# sam4_iot.net
KiCad netlist of a schematic drawn in EAGLE
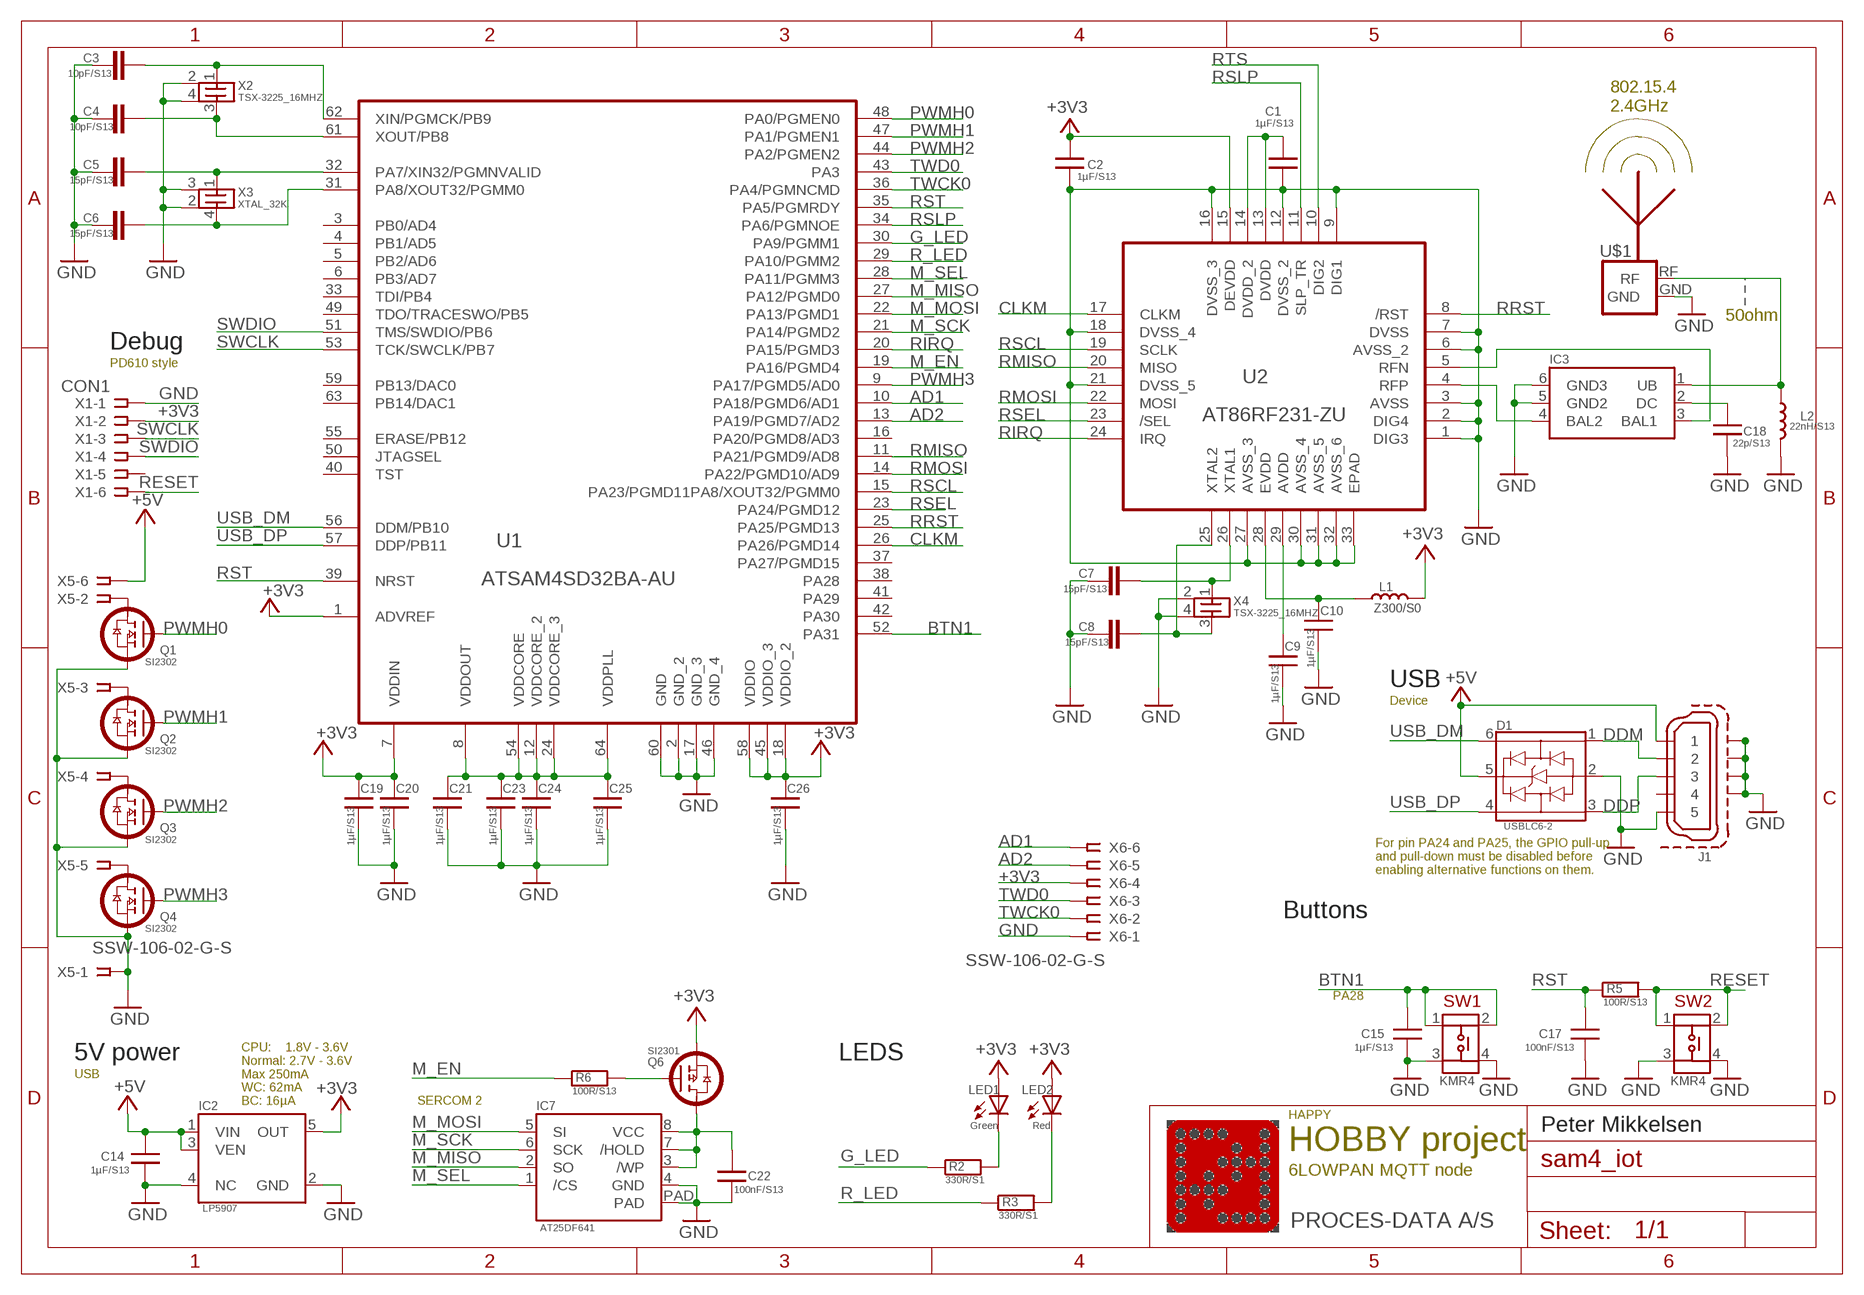
[diagram p0: schematic, sheet 1]

(export (version "E")
  (design (tool "Eeschema 10.0.6"))
  (components
    (comp (ref "C1")
      (value "1µF/S13")
      (footprint "eagle-import:C0603")
      (libsource (lib "eagle-import") (part "C-EUC0603"))
    )
    (comp (ref "C2")
      (value "1µF/S13")
      (footprint "eagle-import:C0603")
      (libsource (lib "eagle-import") (part "C-EUC0603"))
    )
    (comp (ref "C3")
      (value "10pF/S13")
      (footprint "eagle-import:C0603")
      (libsource (lib "eagle-import") (part "rcl_334_C-EUC0603"))
    )
    (comp (ref "C4")
      (value "10pF/S13")
      (footprint "eagle-import:C0603")
      (libsource (lib "eagle-import") (part "rcl_334_C-EUC0603"))
    )
    (comp (ref "C5")
      (value "15pF/S13")
      (footprint "eagle-import:C0603")
      (libsource (lib "eagle-import") (part "rcl_334_C-EUC0603"))
    )
    (comp (ref "C6")
      (value "15pF/S13")
      (footprint "eagle-import:C0603")
      (libsource (lib "eagle-import") (part "rcl_334_C-EUC0603"))
    )
    (comp (ref "C7")
      (value "15pF/S13")
      (footprint "eagle-import:C0603")
      (libsource (lib "eagle-import") (part "rcl_334_C-EUC0603"))
    )
    (comp (ref "C8")
      (value "15pF/S13")
      (footprint "eagle-import:C0603")
      (libsource (lib "eagle-import") (part "rcl_334_C-EUC0603"))
    )
    (comp (ref "C9")
      (value "1µF/S13")
      (footprint "eagle-import:C0603")
      (libsource (lib "eagle-import") (part "C-EUC0603"))
    )
    (comp (ref "C10")
      (value "1µF/S13")
      (footprint "eagle-import:C0603")
      (libsource (lib "eagle-import") (part "C-EUC0603"))
    )
    (comp (ref "C14")
      (value "1µF/S13")
      (footprint "eagle-import:C0603")
      (libsource (lib "eagle-import") (part "C-EUC0603"))
    )
    (comp (ref "C15")
      (value "1µF/S13")
      (footprint "eagle-import:C0603")
      (libsource (lib "eagle-import") (part "C-EUC0603"))
    )
    (comp (ref "C17")
      (value "100nF/S13")
      (footprint "eagle-import:C0603")
      (libsource (lib "eagle-import") (part "C-EUC0603"))
    )
    (comp (ref "C18")
      (value "22p/S13")
      (footprint "eagle-import:C0603")
      (libsource (lib "eagle-import") (part "C-EUC0603"))
    )
    (comp (ref "C19")
      (value "1µF/S13")
      (footprint "eagle-import:C0603")
      (libsource (lib "eagle-import") (part "C-EUC0603"))
    )
    (comp (ref "C20")
      (value "1µF/S13")
      (footprint "eagle-import:C0603")
      (libsource (lib "eagle-import") (part "C-EUC0603"))
    )
    (comp (ref "C21")
      (value "1µF/S13")
      (footprint "eagle-import:C0603")
      (libsource (lib "eagle-import") (part "C-EUC0603"))
    )
    (comp (ref "C22")
      (value "100nF/S13")
      (footprint "eagle-import:C0603")
      (libsource (lib "eagle-import") (part "C-EUC0603"))
    )
    (comp (ref "C23")
      (value "1µF/S13")
      (footprint "eagle-import:C0603")
      (libsource (lib "eagle-import") (part "C-EUC0603"))
    )
    (comp (ref "C24")
      (value "1µF/S13")
      (footprint "eagle-import:C0603")
      (libsource (lib "eagle-import") (part "C-EUC0603"))
    )
    (comp (ref "C25")
      (value "1µF/S13")
      (footprint "eagle-import:C0603")
      (libsource (lib "eagle-import") (part "C-EUC0603"))
    )
    (comp (ref "C26")
      (value "1µF/S13")
      (footprint "eagle-import:C0603")
      (libsource (lib "eagle-import") (part "C-EUC0603"))
    )
    (comp (ref "D1")
      (value "USBLC6-2")
      (footprint "eagle-import:SOT_6")
      (libsource (lib "eagle-import") (part "USBLC6-2"))
    )
    (comp (ref "IC2")
      (value "LP5907")
      (footprint "eagle-import:SOT23-5")
      (libsource (lib "eagle-import") (part "LP5907"))
    )
    (comp (ref "IC3")
      (value "BALUN")
      (footprint "eagle-import:2450BM15A0002")
      (libsource (lib "eagle-import") (part "BALUN"))
    )
    (comp (ref "IC7")
      (value "AT25DF641")
      (footprint "eagle-import:VDFN_8MW1")
      (libsource (lib "eagle-import") (part "AT25DF641"))
    )
    (comp (ref "J1")
      (value "MICROUSB")
      (footprint "eagle-import:MICROUSB")
      (libsource (lib "eagle-import") (part "MICROUSB"))
    )
    (comp (ref "L1")
      (value "Z300/S0")
      (footprint "eagle-import:L0603")
      (libsource (lib "eagle-import") (part "L0603"))
    )
    (comp (ref "L2")
      (value "22nH/S13")
      (footprint "eagle-import:L0603")
      (libsource (lib "eagle-import") (part "L0603"))
    )
    (comp (ref "LED1")
      (value "Green")
      (footprint "eagle-import:OSRAM-MINI-TOP-LED")
      (libsource (lib "eagle-import") (part "LEDMINI-TOP"))
    )
    (comp (ref "LED2")
      (value "Red")
      (footprint "eagle-import:OSRAM-MINI-TOP-LED")
      (libsource (lib "eagle-import") (part "LEDMINI-TOP"))
    )
    (comp (ref "Q1")
      (value "SI2302")
      (footprint "eagle-import:TO-236(SOT23)")
      (libsource (lib "eagle-import") (part "SI2302"))
    )
    (comp (ref "Q2")
      (value "SI2302")
      (footprint "eagle-import:TO-236(SOT23)")
      (libsource (lib "eagle-import") (part "SI2302"))
    )
    (comp (ref "Q3")
      (value "SI2302")
      (footprint "eagle-import:TO-236(SOT23)")
      (libsource (lib "eagle-import") (part "SI2302"))
    )
    (comp (ref "Q4")
      (value "SI2302")
      (footprint "eagle-import:TO-236(SOT23)")
      (libsource (lib "eagle-import") (part "SI2302"))
    )
    (comp (ref "Q6")
      (value "SI2301")
      (footprint "eagle-import:TO-236(SOT23)")
      (libsource (lib "eagle-import") (part "SI2301"))
    )
    (comp (ref "R2")
      (value "330R/S1")
      (footprint "eagle-import:R1206")
      (libsource (lib "eagle-import") (part "R-EU_R1206"))
    )
    (comp (ref "R3")
      (value "330R/S1")
      (footprint "eagle-import:R1206")
      (libsource (lib "eagle-import") (part "R-EU_R1206"))
    )
    (comp (ref "R5")
      (value "100R/S13")
      (footprint "eagle-import:R0603")
      (libsource (lib "eagle-import") (part "R-EU_R0603"))
    )
    (comp (ref "R6")
      (value "100R/S13")
      (footprint "eagle-import:R0603")
      (libsource (lib "eagle-import") (part "R-EU_R0603"))
    )
    (comp (ref "SW1")
      (value "KMR4")
      (footprint "eagle-import:KMR4")
      (libsource (lib "eagle-import") (part "KMR4"))
    )
    (comp (ref "SW2")
      (value "KMR4")
      (footprint "eagle-import:KMR4")
      (libsource (lib "eagle-import") (part "KMR4"))
    )
    (comp (ref "U$1")
      (value "ANTENNA_1RIGHT")
      (footprint "eagle-import:SWRA117D_RIGHT")
      (libsource (lib "eagle-import") (part "ANTENNA_1RIGHT"))
    )
    (comp (ref "U1")
      (value "ATSAM4SD32BA-AU")
      (footprint "eagle-import:QFP50P1200X1200X160-64N")
      (fields (field (name "MPN") "ATSAM3S4BA-AU"))
      (libsource (lib "eagle-import") (part "ATSAM4SD32BA-AU"))
    )
    (comp (ref "U2")
      (value "AT86RF231-ZU")
      (footprint "eagle-import:QFN50P500X500X100-32N")
      (libsource (lib "eagle-import") (part "AT86RF231-ZU"))
    )
    (comp (ref "X1")
      (value "CON1")
      (footprint "eagle-import:SSW-103-02-S-D")
      (fields (field (name "MPN") "SSW-103-02-S-D"))
      (libsource (lib "eagle-import") (part "SSW-103-02-S-D"))
    )
    (comp (ref "X2")
      (value "TSX-3225_16MHZ")
      (footprint "eagle-import:TSX-3225")
      (libsource (lib "eagle-import") (part "TSX-3225_16MHZ"))
    )
    (comp (ref "X3")
      (value "XTAL_32K")
      (footprint "eagle-import:CM200S")
      (libsource (lib "eagle-import") (part "XTAL_32K"))
    )
    (comp (ref "X4")
      (value "TSX-3225_16MHZ")
      (footprint "eagle-import:TSX-3225")
      (libsource (lib "eagle-import") (part "TSX-3225_16MHZ"))
    )
    (comp (ref "X5")
      (value "SSW-106-02-G-S")
      (footprint "eagle-import:SSW-106-02-G-S")
      (fields (field (name "MF") "Samtec Inc."))
      (libsource (lib "eagle-import") (part "SSW-106-02-G-S"))
    )
    (comp (ref "X6")
      (value "SSW-106-02-G-S")
      (footprint "eagle-import:SSW-106-02-G-S")
      (fields (field (name "MF") "Samtec Inc."))
      (libsource (lib "eagle-import") (part "SSW-106-02-G-S"))
    )
  )
  (nets
    (net (code "1") (name "+3V3") (class "Default")
      (node (ref "C19") (pin "1") (pinfunction "1_1") (pintype "passive"))
      (node (ref "C2") (pin "1") (pinfunction "1_1") (pintype "passive"))
      (node (ref "C20") (pin "1") (pinfunction "1_1") (pintype "passive"))
      (node (ref "C26") (pin "1") (pinfunction "1_1") (pintype "passive"))
      (node (ref "IC2") (pin "5") (pinfunction "OUT_5") (pintype "bidirectional"))
      (node (ref "L1") (pin "P$1") (pinfunction "1_P$1") (pintype "bidirectional"))
      (node (ref "LED1") (pin "A") (pinfunction "A_A") (pintype "passive"))
      (node (ref "LED2") (pin "A") (pinfunction "A_A") (pintype "passive"))
      (node (ref "Q6") (pin "3") (pinfunction "S_3") (pintype "bidirectional"))
      (node (ref "U1") (pin "1") (pinfunction "ADVREF_1") (pintype "input"))
      (node (ref "U1") (pin "18") (pinfunction "VDDIO_2_18") (pintype "power_in"))
      (node (ref "U1") (pin "45") (pinfunction "VDDIO_3_45") (pintype "power_in"))
      (node (ref "U1") (pin "58") (pinfunction "VDDIO_58") (pintype "power_in"))
      (node (ref "U1") (pin "7") (pinfunction "VDDIN_7") (pintype "power_in"))
      (node (ref "U2") (pin "15") (pinfunction "DEVDD_15") (pintype "power_in"))
      (node (ref "X1") (pin "2") (pinfunction "1_2") (pintype "passive"))
      (node (ref "X6") (pin "4") (pinfunction "1_4") (pintype "passive"))
    )
    (net (code "2") (name "+5V") (class "Default")
      (node (ref "C14") (pin "1") (pinfunction "1_1") (pintype "passive"))
      (node (ref "D1") (pin "5") (pinfunction "5_5") (pintype "bidirectional"))
      (node (ref "IC2") (pin "1") (pinfunction "VIN_1") (pintype "bidirectional"))
      (node (ref "IC2") (pin "3") (pinfunction "VEN_3") (pintype "bidirectional"))
      (node (ref "J1") (pin "1") (pinfunction "1_1") (pintype "bidirectional"))
      (node (ref "X5") (pin "6") (pinfunction "1_6") (pintype "passive"))
    )
    (net (code "3") (name "/AD1") (class "Default")
      (node (ref "U1") (pin "10") (pinfunction "PA18/PGMD6/AD1_10") (pintype "bidirectional"))
      (node (ref "X6") (pin "6") (pinfunction "1_6") (pintype "passive"))
    )
    (net (code "4") (name "/AD2") (class "Default")
      (node (ref "U1") (pin "13") (pinfunction "PA19/PGMD7/AD2_13") (pintype "bidirectional"))
      (node (ref "X6") (pin "5") (pinfunction "1_5") (pintype "passive"))
    )
    (net (code "5") (name "/BTN1") (class "Default")
      (node (ref "C15") (pin "1") (pinfunction "1_1") (pintype "passive"))
      (node (ref "SW1") (pin "1") (pinfunction "1_1") (pintype "bidirectional"))
      (node (ref "SW1") (pin "2") (pinfunction "3_2") (pintype "bidirectional"))
      (node (ref "U1") (pin "52") (pinfunction "PA31_52") (pintype "bidirectional"))
    )
    (net (code "6") (name "/CLKM") (class "Default")
      (node (ref "U1") (pin "26") (pinfunction "PA26/PGMD14_26") (pintype "bidirectional"))
      (node (ref "U2") (pin "17") (pinfunction "CLKM_17") (pintype "input"))
    )
    (net (code "7") (name "/DDM") (class "Default")
      (node (ref "D1") (pin "1") (pinfunction "1_1") (pintype "bidirectional"))
      (node (ref "J1") (pin "2") (pinfunction "2_2") (pintype "bidirectional"))
    )
    (net (code "8") (name "/DDP") (class "Default")
      (node (ref "D1") (pin "3") (pinfunction "3_3") (pintype "bidirectional"))
      (node (ref "J1") (pin "3") (pinfunction "3_3") (pintype "bidirectional"))
    )
    (net (code "9") (name "/G_LED") (class "Default")
      (node (ref "R2") (pin "1") (pinfunction "1_1") (pintype "passive"))
      (node (ref "U1") (pin "30") (pinfunction "PA9/PGMM1_30") (pintype "bidirectional"))
    )
    (net (code "10") (name "/M_EN") (class "Default")
      (node (ref "R6") (pin "1") (pinfunction "1_1") (pintype "passive"))
      (node (ref "U1") (pin "19") (pinfunction "PA16/PGMD4_19") (pintype "bidirectional"))
    )
    (net (code "11") (name "/M_MISO") (class "Default")
      (node (ref "IC7") (pin "2") (pinfunction "SO_2") (pintype "bidirectional"))
      (node (ref "U1") (pin "27") (pinfunction "PA12/PGMD0_27") (pintype "bidirectional"))
    )
    (net (code "12") (name "/M_MOSI") (class "Default")
      (node (ref "IC7") (pin "5") (pinfunction "SI_5") (pintype "bidirectional"))
      (node (ref "U1") (pin "22") (pinfunction "PA13/PGMD1_22") (pintype "bidirectional"))
    )
    (net (code "13") (name "/M_SCK") (class "Default")
      (node (ref "IC7") (pin "6") (pinfunction "SCK_6") (pintype "bidirectional"))
      (node (ref "U1") (pin "21") (pinfunction "PA14/PGMD2_21") (pintype "bidirectional"))
    )
    (net (code "14") (name "/M_SEL") (class "Default")
      (node (ref "IC7") (pin "1") (pinfunction "/CS_1") (pintype "bidirectional"))
      (node (ref "U1") (pin "28") (pinfunction "PA11/PGMM3_28") (pintype "bidirectional"))
    )
    (net (code "15") (name "/PWMH0") (class "Default")
      (node (ref "Q1") (pin "1") (pinfunction "G_1") (pintype "bidirectional"))
      (node (ref "U1") (pin "48") (pinfunction "PA0/PGMEN0_48") (pintype "bidirectional"))
    )
    (net (code "16") (name "/PWMH1") (class "Default")
      (node (ref "Q2") (pin "1") (pinfunction "G_1") (pintype "bidirectional"))
      (node (ref "U1") (pin "47") (pinfunction "PA1/PGMEN1_47") (pintype "bidirectional"))
    )
    (net (code "17") (name "/PWMH2") (class "Default")
      (node (ref "Q3") (pin "1") (pinfunction "G_1") (pintype "bidirectional"))
      (node (ref "U1") (pin "44") (pinfunction "PA2/PGMEN2_44") (pintype "bidirectional"))
    )
    (net (code "18") (name "/PWMH3") (class "Default")
      (node (ref "Q4") (pin "1") (pinfunction "G_1") (pintype "bidirectional"))
      (node (ref "U1") (pin "9") (pinfunction "PA17/PGMD5/AD0_9") (pintype "bidirectional"))
    )
    (net (code "19") (name "/RESET") (class "Default")
      (node (ref "R5") (pin "2") (pinfunction "2_2") (pintype "passive"))
      (node (ref "SW2") (pin "1") (pinfunction "1_1") (pintype "bidirectional"))
      (node (ref "SW2") (pin "2") (pinfunction "3_2") (pintype "bidirectional"))
      (node (ref "X1") (pin "6") (pinfunction "1_6") (pintype "passive"))
    )
    (net (code "20") (name "/RIRQ") (class "Default")
      (node (ref "U1") (pin "20") (pinfunction "PA15/PGMD3_20") (pintype "bidirectional"))
      (node (ref "U2") (pin "24") (pinfunction "IRQ_24") (pintype "input"))
    )
    (net (code "21") (name "/RMISO") (class "Default")
      (node (ref "U1") (pin "11") (pinfunction "PA21/PGMD9/AD8_11") (pintype "bidirectional"))
      (node (ref "U2") (pin "20") (pinfunction "MISO_20") (pintype "output"))
    )
    (net (code "22") (name "/RMOSI") (class "Default")
      (node (ref "U1") (pin "14") (pinfunction "PA22/PGMD10/AD9_14") (pintype "bidirectional"))
      (node (ref "U2") (pin "22") (pinfunction "MOSI_22") (pintype "input"))
    )
    (net (code "23") (name "/RRST") (class "Default")
      (node (ref "U1") (pin "25") (pinfunction "PA25/PGMD13_25") (pintype "bidirectional"))
      (node (ref "U2") (pin "8") (pinfunction "/RST_8") (pintype "input"))
    )
    (net (code "24") (name "/RSCL") (class "Default")
      (node (ref "U1") (pin "15") (pinfunction "PA23/PGMD11PA8/XOUT32/PGMM0_15") (pintype "bidirectional"))
      (node (ref "U2") (pin "19") (pinfunction "SCLK_19") (pintype "input"))
    )
    (net (code "25") (name "/RSEL") (class "Default")
      (node (ref "U1") (pin "23") (pinfunction "PA24/PGMD12_23") (pintype "bidirectional"))
      (node (ref "U2") (pin "23") (pinfunction "/SEL_23") (pintype "input"))
    )
    (net (code "26") (name "/RSLP") (class "Default")
      (node (ref "U1") (pin "34") (pinfunction "PA6/PGMNOE_34") (pintype "bidirectional"))
      (node (ref "U2") (pin "11") (pinfunction "SLP_TR_11") (pintype "input"))
    )
    (net (code "27") (name "/RST") (class "Default")
      (node (ref "C17") (pin "1") (pinfunction "1_1") (pintype "passive"))
      (node (ref "R5") (pin "1") (pinfunction "1_1") (pintype "passive"))
      (node (ref "U1") (pin "35") (pinfunction "PA5/PGMRDY_35") (pintype "bidirectional"))
      (node (ref "U1") (pin "39") (pinfunction "NRST_39") (pintype "bidirectional"))
    )
    (net (code "28") (name "/RTS") (class "Default")
      (node (ref "U2") (pin "10") (pinfunction "DIG2_10") (pintype "output"))
    )
    (net (code "29") (name "/R_LED") (class "Default")
      (node (ref "R3") (pin "1") (pinfunction "1_1") (pintype "passive"))
      (node (ref "U1") (pin "29") (pinfunction "PA10/PGMM2_29") (pintype "bidirectional"))
    )
    (net (code "30") (name "/SWCLK") (class "Default")
      (node (ref "U1") (pin "53") (pinfunction "TCK/SWCLK/PB7_53") (pintype "bidirectional"))
      (node (ref "X1") (pin "3") (pinfunction "1_3") (pintype "passive"))
    )
    (net (code "31") (name "/SWDIO") (class "Default")
      (node (ref "U1") (pin "51") (pinfunction "TMS/SWDIO/PB6_51") (pintype "bidirectional"))
      (node (ref "X1") (pin "4") (pinfunction "1_4") (pintype "passive"))
    )
    (net (code "32") (name "/TWCK0") (class "Default")
      (node (ref "U1") (pin "36") (pinfunction "PA4/PGMNCMD_36") (pintype "bidirectional"))
      (node (ref "X6") (pin "2") (pinfunction "1_2") (pintype "passive"))
    )
    (net (code "33") (name "/TWD0") (class "Default")
      (node (ref "U1") (pin "43") (pinfunction "PA3_43") (pintype "bidirectional"))
      (node (ref "X6") (pin "3") (pinfunction "1_3") (pintype "passive"))
    )
    (net (code "34") (name "/USB_DM") (class "Default")
      (node (ref "D1") (pin "6") (pinfunction "6_6") (pintype "bidirectional"))
      (node (ref "U1") (pin "56") (pinfunction "DDM/PB10_56") (pintype "bidirectional"))
    )
    (net (code "35") (name "/USB_DP") (class "Default")
      (node (ref "D1") (pin "4") (pinfunction "4_4") (pintype "bidirectional"))
      (node (ref "U1") (pin "57") (pinfunction "DDP/PB11_57") (pintype "bidirectional"))
    )
    (net (code "36") (name "GND") (class "Default")
      (node (ref "C1") (pin "2") (pinfunction "2_2") (pintype "passive"))
      (node (ref "C10") (pin "2") (pinfunction "2_2") (pintype "passive"))
      (node (ref "C14") (pin "2") (pinfunction "2_2") (pintype "passive"))
      (node (ref "C15") (pin "2") (pinfunction "2_2") (pintype "passive"))
      (node (ref "C17") (pin "2") (pinfunction "2_2") (pintype "passive"))
      (node (ref "C18") (pin "2") (pinfunction "2_2") (pintype "passive"))
      (node (ref "C19") (pin "2") (pinfunction "2_2") (pintype "passive"))
      (node (ref "C2") (pin "2") (pinfunction "2_2") (pintype "passive"))
      (node (ref "C20") (pin "2") (pinfunction "2_2") (pintype "passive"))
      (node (ref "C21") (pin "2") (pinfunction "2_2") (pintype "passive"))
      (node (ref "C22") (pin "2") (pinfunction "2_2") (pintype "passive"))
      (node (ref "C23") (pin "2") (pinfunction "2_2") (pintype "passive"))
      (node (ref "C24") (pin "2") (pinfunction "2_2") (pintype "passive"))
      (node (ref "C25") (pin "2") (pinfunction "2_2") (pintype "passive"))
      (node (ref "C26") (pin "2") (pinfunction "2_2") (pintype "passive"))
      (node (ref "C3") (pin "1") (pinfunction "1_1") (pintype "passive"))
      (node (ref "C4") (pin "1") (pinfunction "1_1") (pintype "passive"))
      (node (ref "C5") (pin "1") (pinfunction "1_1") (pintype "passive"))
      (node (ref "C6") (pin "1") (pinfunction "1_1") (pintype "passive"))
      (node (ref "C7") (pin "1") (pinfunction "1_1") (pintype "passive"))
      (node (ref "C8") (pin "1") (pinfunction "1_1") (pintype "passive"))
      (node (ref "C9") (pin "2") (pinfunction "2_2") (pintype "passive"))
      (node (ref "D1") (pin "2") (pinfunction "2_2") (pintype "bidirectional"))
      (node (ref "IC2") (pin "2") (pinfunction "GND_2") (pintype "bidirectional"))
      (node (ref "IC2") (pin "4") (pinfunction "NC_4") (pintype "bidirectional"))
      (node (ref "IC3") (pin "5") (pinfunction "GND2_5") (pintype "bidirectional"))
      (node (ref "IC3") (pin "6") (pinfunction "GND3_6") (pintype "bidirectional"))
      (node (ref "IC7") (pin "4") (pinfunction "GND_4") (pintype "bidirectional"))
      (node (ref "IC7") (pin "PAD") (pinfunction "PAD_PAD") (pintype "bidirectional"))
      (node (ref "J1") (pin "5") (pinfunction "5_5") (pintype "bidirectional"))
      (node (ref "J1") (pin "6") (pinfunction "6_6") (pintype "bidirectional"))
      (node (ref "J1") (pin "7") (pinfunction "7_7") (pintype "bidirectional"))
      (node (ref "J1") (pin "8") (pinfunction "8_8") (pintype "bidirectional"))
      (node (ref "J1") (pin "9") (pinfunction "9_9") (pintype "bidirectional"))
      (node (ref "L2") (pin "P$1") (pinfunction "1_P$1") (pintype "bidirectional"))
      (node (ref "Q1") (pin "2") (pinfunction "S_2") (pintype "bidirectional"))
      (node (ref "Q2") (pin "2") (pinfunction "S_2") (pintype "bidirectional"))
      (node (ref "Q3") (pin "2") (pinfunction "S_2") (pintype "bidirectional"))
      (node (ref "Q4") (pin "2") (pinfunction "S_2") (pintype "bidirectional"))
      (node (ref "SW1") (pin "3") (pinfunction "2_3") (pintype "bidirectional"))
      (node (ref "SW1") (pin "4") (pinfunction "4_4") (pintype "bidirectional"))
      (node (ref "SW2") (pin "3") (pinfunction "2_3") (pintype "bidirectional"))
      (node (ref "SW2") (pin "4") (pinfunction "4_4") (pintype "bidirectional"))
      (node (ref "U$1") (pin "GND") (pinfunction "GND_GND") (pintype "passive"))
      (node (ref "U1") (pin "17") (pinfunction "GND_3_17") (pintype "passive"))
      (node (ref "U1") (pin "2") (pinfunction "GND_2_2") (pintype "passive"))
      (node (ref "U1") (pin "46") (pinfunction "GND_4_46") (pintype "passive"))
      (node (ref "U1") (pin "60") (pinfunction "GND_60") (pintype "passive"))
      (node (ref "U2") (pin "1") (pinfunction "DIG3_1") (pintype "output"))
      (node (ref "U2") (pin "12") (pinfunction "DVSS_2_12") (pintype "power_in"))
      (node (ref "U2") (pin "16") (pinfunction "DVSS_3_16") (pintype "power_in"))
      (node (ref "U2") (pin "18") (pinfunction "DVSS_4_18") (pintype "power_in"))
      (node (ref "U2") (pin "2") (pinfunction "DIG4_2") (pintype "output"))
      (node (ref "U2") (pin "21") (pinfunction "DVSS_5_21") (pintype "power_in"))
      (node (ref "U2") (pin "27") (pinfunction "AVSS_3_27") (pintype "power_in"))
      (node (ref "U2") (pin "3") (pinfunction "AVSS_3") (pintype "power_in"))
      (node (ref "U2") (pin "30") (pinfunction "AVSS_4_30") (pintype "power_in"))
      (node (ref "U2") (pin "31") (pinfunction "AVSS_5_31") (pintype "power_in"))
      (node (ref "U2") (pin "32") (pinfunction "AVSS_6_32") (pintype "power_in"))
      (node (ref "U2") (pin "33") (pinfunction "EPAD_33") (pintype "passive"))
      (node (ref "U2") (pin "6") (pinfunction "AVSS_2_6") (pintype "power_in"))
      (node (ref "U2") (pin "7") (pinfunction "DVSS_7") (pintype "power_in"))
      (node (ref "U2") (pin "9") (pinfunction "DIG1_9") (pintype "output"))
      (node (ref "X1") (pin "1") (pinfunction "1_1") (pintype "passive"))
      (node (ref "X2") (pin "2") (pinfunction "GND1_2") (pintype "bidirectional"))
      (node (ref "X2") (pin "4") (pinfunction "GND2_4") (pintype "bidirectional"))
      (node (ref "X3") (pin "2") (pinfunction "GND2_2") (pintype "bidirectional"))
      (node (ref "X3") (pin "3") (pinfunction "GND1_3") (pintype "bidirectional"))
      (node (ref "X4") (pin "2") (pinfunction "GND1_2") (pintype "bidirectional"))
      (node (ref "X4") (pin "4") (pinfunction "GND2_4") (pintype "bidirectional"))
      (node (ref "X5") (pin "1") (pinfunction "1_1") (pintype "passive"))
      (node (ref "X6") (pin "1") (pinfunction "1_1") (pintype "passive"))
    )
    (net (code "37") (name "Net-(IC3-BAL1)") (class "Default")
      (node (ref "IC3") (pin "3") (pinfunction "BAL1_3") (pintype "bidirectional"))
      (node (ref "U2") (pin "5") (pinfunction "RFN_5") (pintype "input"))
    )
    (net (code "38") (name "Net-(IC3-BAL2)") (class "Default")
      (node (ref "IC3") (pin "4") (pinfunction "BAL2_4") (pintype "bidirectional"))
      (node (ref "U2") (pin "4") (pinfunction "RFP_4") (pintype "input"))
    )
    (net (code "39") (name "Net-(IC3-DC)") (class "Default")
      (node (ref "C18") (pin "1") (pinfunction "1_1") (pintype "passive"))
      (node (ref "IC3") (pin "2") (pinfunction "DC_2") (pintype "bidirectional"))
    )
    (net (code "40") (name "Net-(IC3-UB)") (class "Default")
      (node (ref "IC3") (pin "1") (pinfunction "UB_1") (pintype "bidirectional"))
      (node (ref "L2") (pin "P$2") (pinfunction "2_P$2") (pintype "bidirectional"))
      (node (ref "U$1") (pin "RF") (pinfunction "RF_RF") (pintype "bidirectional"))
    )
    (net (code "41") (name "Net-(IC7-VCC)") (class "Default")
      (node (ref "C22") (pin "1") (pinfunction "1_1") (pintype "passive"))
      (node (ref "IC7") (pin "3") (pinfunction "/WP_3") (pintype "bidirectional"))
      (node (ref "IC7") (pin "7") (pinfunction "/HOLD_7") (pintype "bidirectional"))
      (node (ref "IC7") (pin "8") (pinfunction "VCC_8") (pintype "bidirectional"))
      (node (ref "Q6") (pin "2") (pinfunction "D_2") (pintype "bidirectional"))
    )
    (net (code "42") (name "Net-(L1-2)") (class "Default")
      (node (ref "C10") (pin "1") (pinfunction "1_1") (pintype "passive"))
      (node (ref "L1") (pin "P$2") (pinfunction "2_P$2") (pintype "bidirectional"))
      (node (ref "U2") (pin "28") (pinfunction "EVDD_28") (pintype "power_in"))
    )
    (net (code "43") (name "Net-(LED1-PadC)") (class "Default")
      (node (ref "LED1") (pin "C") (pinfunction "C_C") (pintype "passive"))
      (node (ref "R2") (pin "2") (pinfunction "2_2") (pintype "passive"))
    )
    (net (code "44") (name "Net-(LED2-PadC)") (class "Default")
      (node (ref "LED2") (pin "C") (pinfunction "C_C") (pintype "passive"))
      (node (ref "R3") (pin "2") (pinfunction "2_2") (pintype "passive"))
    )
    (net (code "45") (name "Net-(Q1-D)") (class "Default")
      (node (ref "Q1") (pin "3") (pinfunction "D_3") (pintype "bidirectional"))
      (node (ref "X5") (pin "2") (pinfunction "1_2") (pintype "passive"))
    )
    (net (code "46") (name "Net-(Q2-D)") (class "Default")
      (node (ref "Q2") (pin "3") (pinfunction "D_3") (pintype "bidirectional"))
      (node (ref "X5") (pin "3") (pinfunction "1_3") (pintype "passive"))
    )
    (net (code "47") (name "Net-(Q3-D)") (class "Default")
      (node (ref "Q3") (pin "3") (pinfunction "D_3") (pintype "bidirectional"))
      (node (ref "X5") (pin "4") (pinfunction "1_4") (pintype "passive"))
    )
    (net (code "48") (name "Net-(Q4-D)") (class "Default")
      (node (ref "Q4") (pin "3") (pinfunction "D_3") (pintype "bidirectional"))
      (node (ref "X5") (pin "5") (pinfunction "1_5") (pintype "passive"))
    )
    (net (code "49") (name "Net-(Q6-G)") (class "Default")
      (node (ref "Q6") (pin "1") (pinfunction "G_1") (pintype "bidirectional"))
      (node (ref "R6") (pin "2") (pinfunction "2_2") (pintype "passive"))
    )
    (net (code "50") (name "Net-(U1-PA7{slash}XIN32{slash}PGMNVALID)") (class "Default")
      (node (ref "C5") (pin "2") (pinfunction "2_2") (pintype "passive"))
      (node (ref "U1") (pin "32") (pinfunction "PA7/XIN32/PGMNVALID_32") (pintype "bidirectional"))
      (node (ref "X3") (pin "1") (pinfunction "X1_1") (pintype "bidirectional"))
    )
    (net (code "51") (name "Net-(U1-PA8{slash}XOUT32{slash}PGMM0)") (class "Default")
      (node (ref "C6") (pin "2") (pinfunction "2_2") (pintype "passive"))
      (node (ref "U1") (pin "31") (pinfunction "PA8/XOUT32/PGMM0_31") (pintype "bidirectional"))
      (node (ref "X3") (pin "4") (pinfunction "X2_4") (pintype "bidirectional"))
    )
    (net (code "52") (name "Net-(U1-VDDCORE)") (class "Default")
      (node (ref "C21") (pin "1") (pinfunction "1_1") (pintype "passive"))
      (node (ref "C23") (pin "1") (pinfunction "1_1") (pintype "passive"))
      (node (ref "C24") (pin "1") (pinfunction "1_1") (pintype "passive"))
      (node (ref "C25") (pin "1") (pinfunction "1_1") (pintype "passive"))
      (node (ref "U1") (pin "12") (pinfunction "VDDCORE_2_12") (pintype "power_in"))
      (node (ref "U1") (pin "24") (pinfunction "VDDCORE_3_24") (pintype "power_in"))
      (node (ref "U1") (pin "54") (pinfunction "VDDCORE_54") (pintype "power_in"))
      (node (ref "U1") (pin "64") (pinfunction "VDDPLL_64") (pintype "power_in"))
      (node (ref "U1") (pin "8") (pinfunction "VDDOUT_8") (pintype "power_in"))
    )
    (net (code "53") (name "Net-(U1-XIN{slash}PGMCK{slash}PB9)") (class "Default")
      (node (ref "C3") (pin "2") (pinfunction "2_2") (pintype "passive"))
      (node (ref "U1") (pin "62") (pinfunction "XIN/PGMCK/PB9_62") (pintype "input"))
      (node (ref "X2") (pin "1") (pinfunction "X1_1") (pintype "bidirectional"))
    )
    (net (code "54") (name "Net-(U1-XOUT{slash}PB8)") (class "Default")
      (node (ref "C4") (pin "2") (pinfunction "2_2") (pintype "passive"))
      (node (ref "U1") (pin "61") (pinfunction "XOUT/PB8_61") (pintype "output"))
      (node (ref "X2") (pin "3") (pinfunction "X2_3") (pintype "bidirectional"))
    )
    (net (code "55") (name "Net-(U2-AVDD)") (class "Default")
      (node (ref "C9") (pin "1") (pinfunction "1_1") (pintype "passive"))
      (node (ref "U2") (pin "29") (pinfunction "AVDD_29") (pintype "power_in"))
    )
    (net (code "56") (name "Net-(U2-DVDD)") (class "Default")
      (node (ref "C1") (pin "1") (pinfunction "1_1") (pintype "passive"))
      (node (ref "U2") (pin "13") (pinfunction "DVDD_13") (pintype "power_in"))
      (node (ref "U2") (pin "14") (pinfunction "DVDD_2_14") (pintype "power_in"))
    )
    (net (code "57") (name "Net-(U2-XTAL1)") (class "Default")
      (node (ref "C7") (pin "2") (pinfunction "2_2") (pintype "passive"))
      (node (ref "U2") (pin "26") (pinfunction "XTAL1_26") (pintype "input"))
      (node (ref "X4") (pin "1") (pinfunction "X1_1") (pintype "bidirectional"))
    )
    (net (code "58") (name "Net-(U2-XTAL2)") (class "Default")
      (node (ref "C8") (pin "2") (pinfunction "2_2") (pintype "passive"))
      (node (ref "U2") (pin "25") (pinfunction "XTAL2_25") (pintype "output"))
      (node (ref "X4") (pin "3") (pinfunction "X2_3") (pintype "bidirectional"))
    )
    (net (code "59") (name "unconnected-(J1-Pad4)") (class "Default")
      (node (ref "J1") (pin "4") (pinfunction "4_4") (pintype "bidirectional"))
    )
    (net (code "60") (name "unconnected-(U1-ERASE{slash}PB12-Pad55)") (class "Default")
      (node (ref "U1") (pin "55") (pinfunction "ERASE/PB12_55") (pintype "bidirectional"))
    )
    (net (code "61") (name "unconnected-(U1-JTAGSEL-Pad50)") (class "Default")
      (node (ref "U1") (pin "50") (pinfunction "JTAGSEL_50") (pintype "input"))
    )
    (net (code "62") (name "unconnected-(U1-PA20{slash}PGMD8{slash}AD3-Pad16)") (class "Default")
      (node (ref "U1") (pin "16") (pinfunction "PA20/PGMD8/AD3_16") (pintype "bidirectional"))
    )
    (net (code "63") (name "unconnected-(U1-PA27{slash}PGMD15-Pad37)") (class "Default")
      (node (ref "U1") (pin "37") (pinfunction "PA27/PGMD15_37") (pintype "bidirectional"))
    )
    (net (code "64") (name "unconnected-(U1-PA28-Pad38)") (class "Default")
      (node (ref "U1") (pin "38") (pinfunction "PA28_38") (pintype "bidirectional"))
    )
    (net (code "65") (name "unconnected-(U1-PA29-Pad41)") (class "Default")
      (node (ref "U1") (pin "41") (pinfunction "PA29_41") (pintype "bidirectional"))
    )
    (net (code "66") (name "unconnected-(U1-PA30-Pad42)") (class "Default")
      (node (ref "U1") (pin "42") (pinfunction "PA30_42") (pintype "bidirectional"))
    )
    (net (code "67") (name "unconnected-(U1-PB0{slash}AD4-Pad3)") (class "Default")
      (node (ref "U1") (pin "3") (pinfunction "PB0/AD4_3") (pintype "bidirectional"))
    )
    (net (code "68") (name "unconnected-(U1-PB1{slash}AD5-Pad4)") (class "Default")
      (node (ref "U1") (pin "4") (pinfunction "PB1/AD5_4") (pintype "bidirectional"))
    )
    (net (code "69") (name "unconnected-(U1-PB2{slash}AD6-Pad5)") (class "Default")
      (node (ref "U1") (pin "5") (pinfunction "PB2/AD6_5") (pintype "bidirectional"))
    )
    (net (code "70") (name "unconnected-(U1-PB3{slash}AD7-Pad6)") (class "Default")
      (node (ref "U1") (pin "6") (pinfunction "PB3/AD7_6") (pintype "bidirectional"))
    )
    (net (code "71") (name "unconnected-(U1-PB13{slash}DAC0-Pad59)") (class "Default")
      (node (ref "U1") (pin "59") (pinfunction "PB13/DAC0_59") (pintype "bidirectional"))
    )
    (net (code "72") (name "unconnected-(U1-PB14{slash}DAC1-Pad63)") (class "Default")
      (node (ref "U1") (pin "63") (pinfunction "PB14/DAC1_63") (pintype "bidirectional"))
    )
    (net (code "73") (name "unconnected-(U1-TDI{slash}PB4-Pad33)") (class "Default")
      (node (ref "U1") (pin "33") (pinfunction "TDI/PB4_33") (pintype "bidirectional"))
    )
    (net (code "74") (name "unconnected-(U1-TDO{slash}TRACESWO{slash}PB5-Pad49)") (class "Default")
      (node (ref "U1") (pin "49") (pinfunction "TDO/TRACESWO/PB5_49") (pintype "bidirectional"))
    )
    (net (code "75") (name "unconnected-(U1-TST-Pad40)") (class "Default")
      (node (ref "U1") (pin "40") (pinfunction "TST_40") (pintype "input"))
    )
    (net (code "76") (name "unconnected-(X1E-1-Pad5)") (class "Default")
      (node (ref "X1") (pin "5") (pinfunction "1_5") (pintype "passive"))
    )
  )
)
